# roboimplantschematic.net
KiCad netlist of a schematic drawn in EAGLE
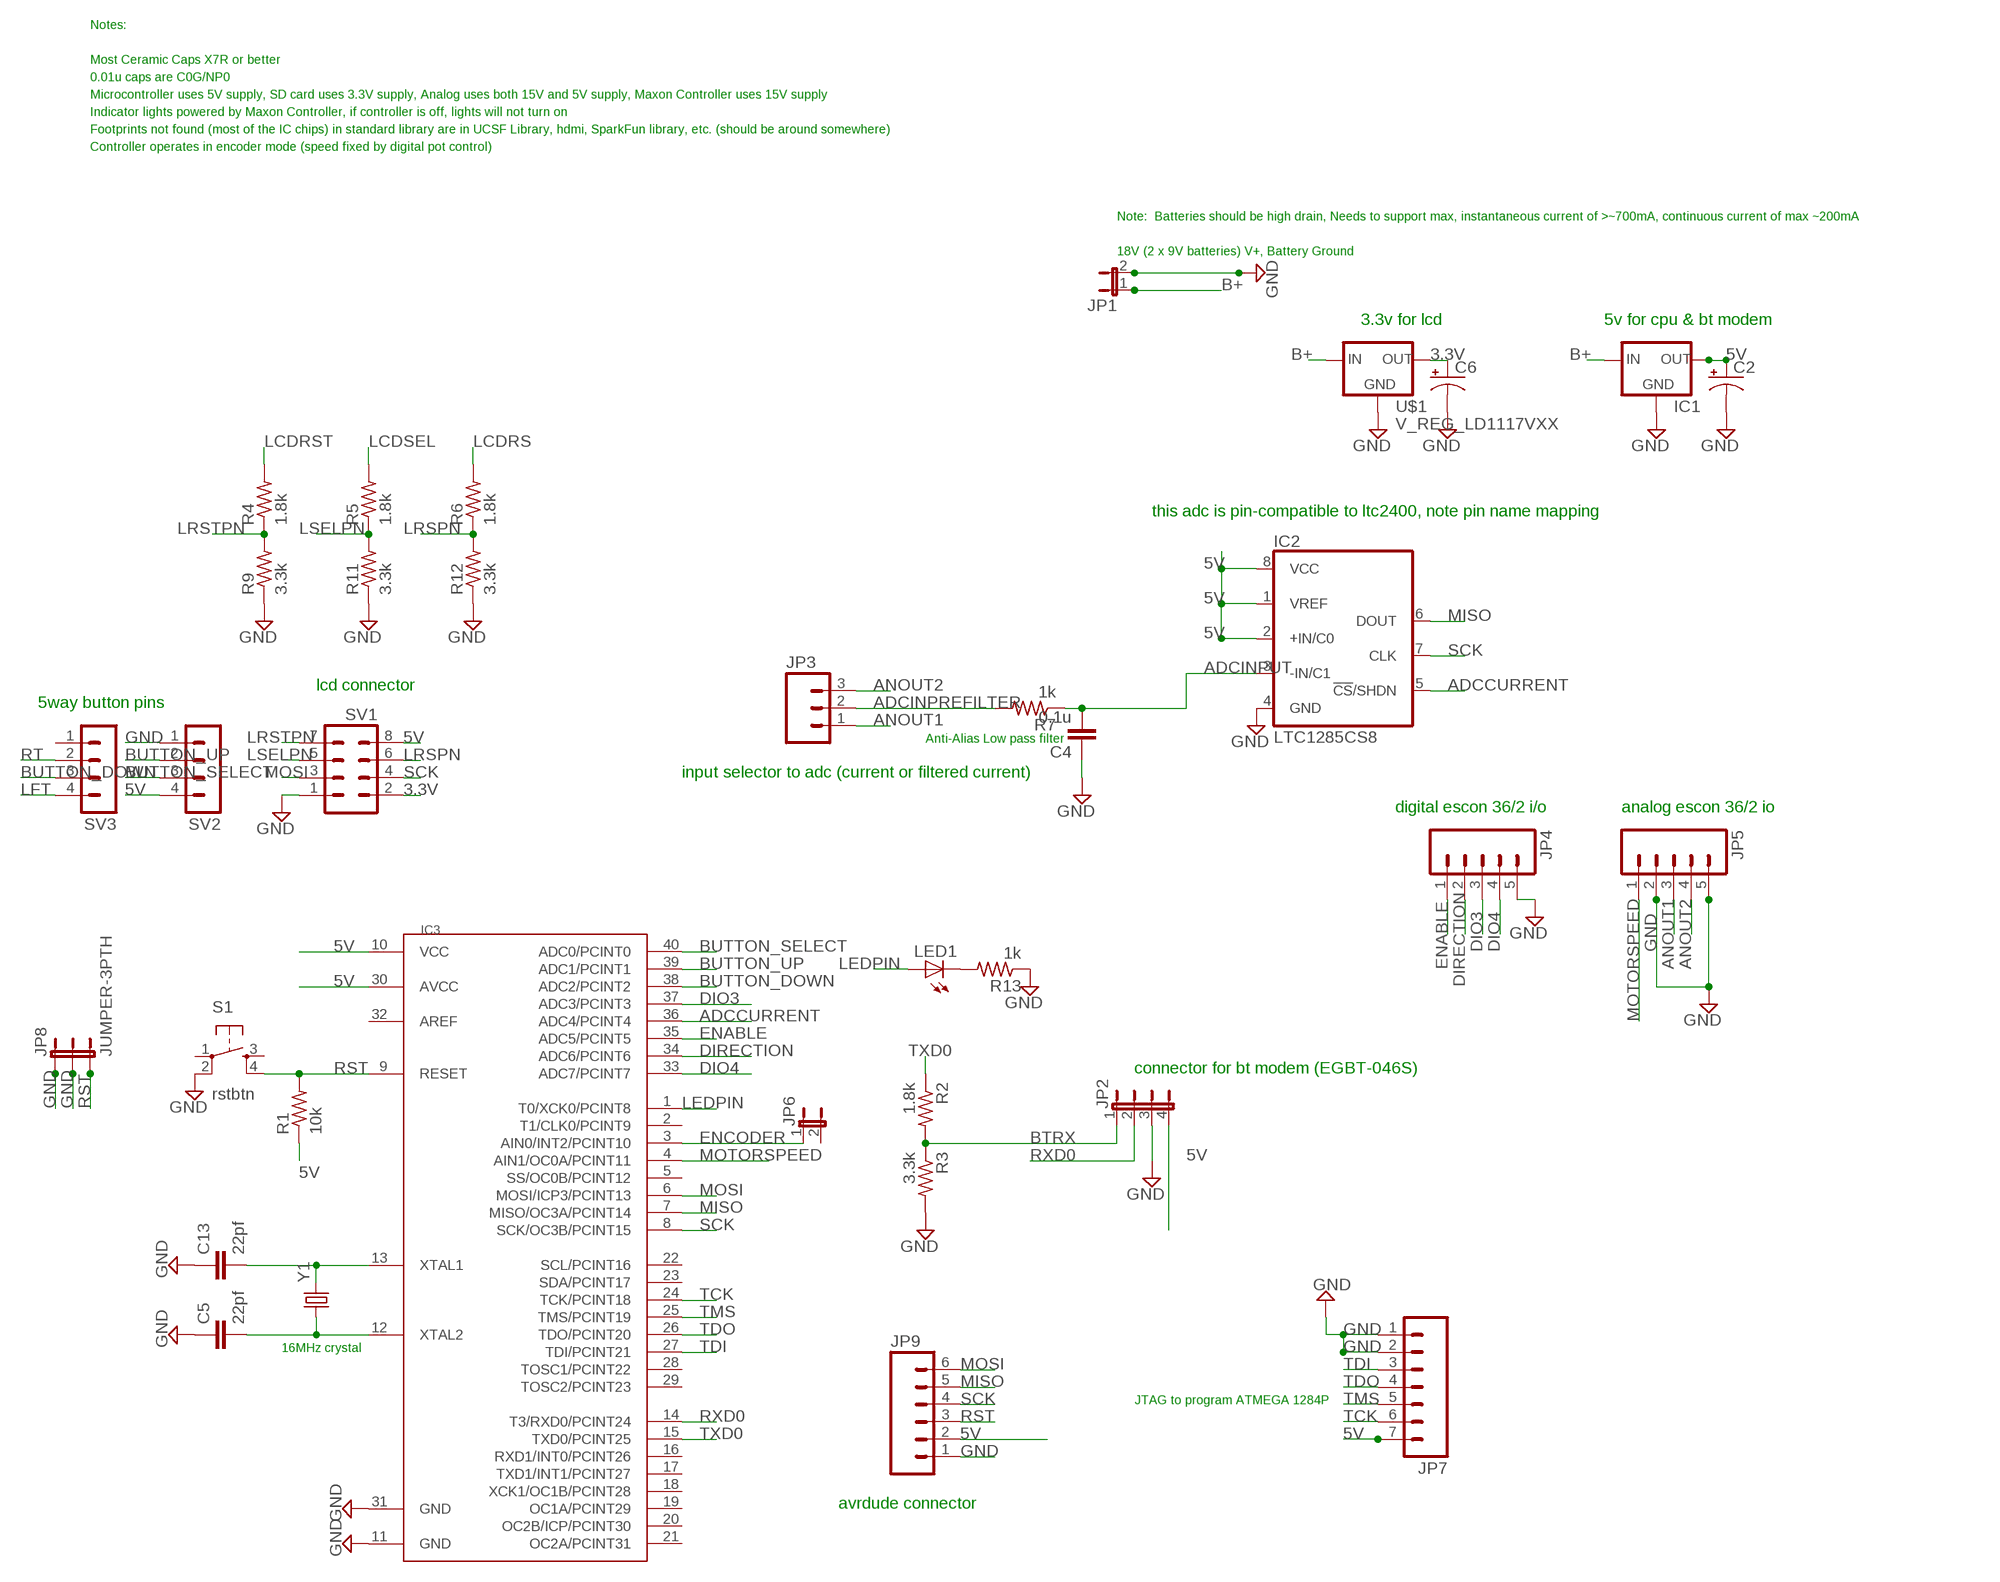
[diagram p0: schematic, sheet 1]

(export (version "E")
  (design (tool "Eeschema 10.0.6"))
  (components
    (comp (ref "C2")
      (value "CAP_POLPTH2")
      (footprint "eagle-import:CPOL-RADIAL-10UF-25V")
      (libsource (lib "eagle-import") (part "CAP_POLPTH2"))
    )
    (comp (ref "C4")
      (value "0.1u")
      (footprint "eagle-import:050X030_025")
      (libsource (lib "eagle-import") (part "050X030_0251"))
    )
    (comp (ref "C5")
      (value "22pf")
      (footprint "eagle-import:050X030_025")
      (libsource (lib "eagle-import") (part "050X030_0251"))
    )
    (comp (ref "C6")
      (value "CAP_POLPTH2")
      (footprint "eagle-import:CPOL-RADIAL-10UF-25V")
      (libsource (lib "eagle-import") (part "CAP_POLPTH2"))
    )
    (comp (ref "C13")
      (value "22pf")
      (footprint "eagle-import:050X030_025")
      (libsource (lib "eagle-import") (part "050X030_0251"))
    )
    (comp (ref "IC1")
      (value "V_REG_78XX-TO-220")
      (footprint "eagle-import:TO-220-ALT")
      (libsource (lib "eagle-import") (part "V_REG_78XX-TO-220"))
    )
    (comp (ref "IC2")
      (value "LTC1285CS8")
      (footprint "eagle-import:SOIC8")
      (libsource (lib "eagle-import") (part "LTC128CS85"))
    )
    (comp (ref "IC3")
      (value "MEGA1284P")
      (footprint "eagle-import:DIL40")
      (libsource (lib "eagle-import") (part "MEGA1284P"))
    )
    (comp (ref "JP1")
      (value "JP1E")
      (footprint "eagle-import:JP1")
      (libsource (lib "eagle-import") (part "JP1E"))
    )
    (comp (ref "JP2")
      (value "JP4E")
      (footprint "eagle-import:JP4")
      (libsource (lib "eagle-import") (part "JP4E"))
    )
    (comp (ref "JP3")
      (value "M03LOCK_LONGPADS")
      (footprint "eagle-import:1X03_LOCK_LONGPADS")
      (libsource (lib "eagle-import") (part "M03LOCK_LONGPADS"))
    )
    (comp (ref "JP4")
      (value "M05PTH_LONGPADS")
      (footprint "eagle-import:1X05_LONGPADS")
      (libsource (lib "eagle-import") (part "M05PTH_LONGPADS"))
    )
    (comp (ref "JP5")
      (value "M05PTH_LONGPADS")
      (footprint "eagle-import:1X05_LONGPADS")
      (libsource (lib "eagle-import") (part "M05PTH_LONGPADS"))
    )
    (comp (ref "JP6")
      (value "JUMPER-2PTH")
      (footprint "eagle-import:1X02")
      (libsource (lib "eagle-import") (part "JUMPER-2PTH"))
    )
    (comp (ref "JP7")
      (value "M07LOCK")
      (footprint "eagle-import:1X07_LOCK")
      (libsource (lib "eagle-import") (part "M07LOCK"))
    )
    (comp (ref "JP8")
      (value "JUMPER-3PTH")
      (footprint "eagle-import:1X03")
      (libsource (lib "eagle-import") (part "JUMPER-3PTH"))
    )
    (comp (ref "JP9")
      (value "M06SIP_LOCK")
      (footprint "eagle-import:1X06-SIP_LOCK")
      (libsource (lib "eagle-import") (part "M06SIP_LOCK"))
    )
    (comp (ref "LED1")
      (value "LED5MM")
      (footprint "eagle-import:LED5MM")
      (libsource (lib "eagle-import") (part "LED5MM"))
    )
    (comp (ref "R1")
      (value "10k")
      (footprint "eagle-import:0204_7")
      (libsource (lib "eagle-import") (part "R-US_0204/7"))
    )
    (comp (ref "R2")
      (value "1.8k")
      (footprint "eagle-import:0207_2V")
      (libsource (lib "eagle-import") (part "R-US_0207/2V"))
    )
    (comp (ref "R3")
      (value "3.3k")
      (footprint "eagle-import:0207_2V")
      (libsource (lib "eagle-import") (part "R-US_0207/2V"))
    )
    (comp (ref "R4")
      (value "1.8k")
      (footprint "eagle-import:0207_2V")
      (libsource (lib "eagle-import") (part "R-US_0207/2V"))
    )
    (comp (ref "R5")
      (value "1.8k")
      (footprint "eagle-import:0207_2V")
      (libsource (lib "eagle-import") (part "R-US_0207/2V"))
    )
    (comp (ref "R6")
      (value "1.8k")
      (footprint "eagle-import:0207_2V")
      (libsource (lib "eagle-import") (part "R-US_0207/2V"))
    )
    (comp (ref "R7")
      (value "1k")
      (footprint "eagle-import:0207_2V")
      (libsource (lib "eagle-import") (part "R-US_0207/2V"))
    )
    (comp (ref "R9")
      (value "3.3k")
      (footprint "eagle-import:0207_2V")
      (libsource (lib "eagle-import") (part "R-US_0207/2V"))
    )
    (comp (ref "R11")
      (value "3.3k")
      (footprint "eagle-import:0207_2V")
      (libsource (lib "eagle-import") (part "R-US_0207/2V"))
    )
    (comp (ref "R12")
      (value "3.3k")
      (footprint "eagle-import:0207_2V")
      (libsource (lib "eagle-import") (part "R-US_0207/2V"))
    )
    (comp (ref "R13")
      (value "1k")
      (footprint "eagle-import:0207_2V")
      (libsource (lib "eagle-import") (part "R-US_0207/2V"))
    )
    (comp (ref "S1")
      (value "rstbtn")
      (footprint "eagle-import:TACTILE-PTH")
      (libsource (lib "eagle-import") (part "TAC_SWITCHPTH"))
    )
    (comp (ref "SV1")
      (value "MA04-2")
      (footprint "eagle-import:MA04-2")
      (libsource (lib "eagle-import") (part "MA04-2"))
    )
    (comp (ref "SV2")
      (value "MA04-1")
      (footprint "eagle-import:MA04-1")
      (libsource (lib "eagle-import") (part "MA04-1"))
    )
    (comp (ref "SV3")
      (value "MA04-1")
      (footprint "eagle-import:MA04-1")
      (libsource (lib "eagle-import") (part "MA04-1"))
    )
    (comp (ref "U$1")
      (value "V_REG_LD1117VXX")
      (footprint "eagle-import:78XXL")
      (libsource (lib "eagle-import") (part "V_REG_LD1117VXX"))
    )
    (comp (ref "Y1")
      (value "CRYSTALHC49US")
      (footprint "eagle-import:HC49US")
      (libsource (lib "eagle-import") (part "CRYSTALHC49US"))
    )
  )
  (nets
    (net (code "1") (name "/3.3V") (class "Default")
      (node (ref "C6") (pin "1") (pinfunction "+_1") (pintype "passive"))
      (node (ref "SV1") (pin "2") (pinfunction "2_2") (pintype "passive"))
      (node (ref "U$1") (pin "GND") (pinfunction "OUT_GND") (pintype "output"))
    )
    (net (code "2") (name "/5V") (class "Default")
      (node (ref "C2") (pin "1") (pinfunction "+_1") (pintype "passive"))
      (node (ref "IC1") (pin "OUT") (pinfunction "OUT_OUT") (pintype "output"))
      (node (ref "IC2") (pin "1") (pinfunction "VREF_1") (pintype "input"))
      (node (ref "IC2") (pin "2") (pinfunction "+IN/C0_2") (pintype "input"))
      (node (ref "IC2") (pin "8") (pinfunction "VCC_8") (pintype "power_in"))
      (node (ref "IC3") (pin "10") (pinfunction "VCC_10") (pintype "bidirectional"))
      (node (ref "IC3") (pin "30") (pinfunction "AVCC_30") (pintype "bidirectional"))
      (node (ref "JP2") (pin "4") (pinfunction "4_4") (pintype "passive"))
      (node (ref "JP7") (pin "7") (pinfunction "7_7") (pintype "passive"))
      (node (ref "JP9") (pin "2") (pinfunction "2_2") (pintype "passive"))
      (node (ref "R1") (pin "1") (pinfunction "1_1") (pintype "passive"))
      (node (ref "SV1") (pin "8") (pinfunction "8_8") (pintype "passive"))
      (node (ref "SV2") (pin "4") (pinfunction "4_4") (pintype "passive"))
    )
    (net (code "3") (name "/ADCCURRENT") (class "Default")
      (node (ref "IC2") (pin "5") (pinfunction "~{CS}/SHDN_5") (pintype "output"))
      (node (ref "IC3") (pin "36") (pinfunction "ADC4/PCINT4_36") (pintype "bidirectional"))
    )
    (net (code "4") (name "/ADCINPREFILTER") (class "Default")
      (node (ref "JP3") (pin "2") (pinfunction "2_2") (pintype "passive"))
      (node (ref "R7") (pin "2") (pinfunction "2_2") (pintype "passive"))
    )
    (net (code "5") (name "/ADCINPUT") (class "Default")
      (node (ref "C4") (pin "2") (pinfunction "2_2") (pintype "passive"))
      (node (ref "IC2") (pin "3") (pinfunction "-IN/C1_3") (pintype "input"))
      (node (ref "R7") (pin "1") (pinfunction "1_1") (pintype "passive"))
    )
    (net (code "6") (name "/ANOUT1") (class "Default")
      (node (ref "JP3") (pin "1") (pinfunction "1_1") (pintype "passive"))
      (node (ref "JP5") (pin "3") (pinfunction "3_3") (pintype "passive"))
    )
    (net (code "7") (name "/ANOUT2") (class "Default")
      (node (ref "JP3") (pin "3") (pinfunction "3_3") (pintype "passive"))
      (node (ref "JP5") (pin "4") (pinfunction "4_4") (pintype "passive"))
    )
    (net (code "8") (name "/B+") (class "Default")
      (node (ref "IC1") (pin "IN") (pinfunction "IN_IN") (pintype "input"))
      (node (ref "JP1") (pin "1") (pinfunction "1_1") (pintype "passive"))
      (node (ref "U$1") (pin "OUT") (pinfunction "IN_OUT") (pintype "input"))
    )
    (net (code "9") (name "/BTRX") (class "Default")
      (node (ref "JP2") (pin "1") (pinfunction "1_1") (pintype "passive"))
      (node (ref "R2") (pin "2") (pinfunction "2_2") (pintype "passive"))
      (node (ref "R3") (pin "1") (pinfunction "1_1") (pintype "passive"))
    )
    (net (code "10") (name "/BUTTON_DOWN") (class "Default")
      (node (ref "IC3") (pin "38") (pinfunction "ADC2/PCINT2_38") (pintype "bidirectional"))
      (node (ref "SV3") (pin "3") (pinfunction "3_3") (pintype "passive"))
    )
    (net (code "11") (name "/BUTTON_SELECT") (class "Default")
      (node (ref "IC3") (pin "40") (pinfunction "ADC0/PCINT0_40") (pintype "bidirectional"))
      (node (ref "SV2") (pin "3") (pinfunction "3_3") (pintype "passive"))
    )
    (net (code "12") (name "/BUTTON_UP") (class "Default")
      (node (ref "IC3") (pin "39") (pinfunction "ADC1/PCINT1_39") (pintype "bidirectional"))
      (node (ref "SV2") (pin "2") (pinfunction "2_2") (pintype "passive"))
    )
    (net (code "13") (name "/DIO3") (class "Default")
      (node (ref "IC3") (pin "37") (pinfunction "ADC3/PCINT3_37") (pintype "bidirectional"))
      (node (ref "JP4") (pin "3") (pinfunction "3_3") (pintype "passive"))
    )
    (net (code "14") (name "/DIO4") (class "Default")
      (node (ref "IC3") (pin "33") (pinfunction "ADC7/PCINT7_33") (pintype "bidirectional"))
      (node (ref "JP4") (pin "4") (pinfunction "4_4") (pintype "passive"))
    )
    (net (code "15") (name "/DIRECTION") (class "Default")
      (node (ref "IC3") (pin "34") (pinfunction "ADC6/PCINT6_34") (pintype "bidirectional"))
      (node (ref "JP4") (pin "2") (pinfunction "2_2") (pintype "passive"))
    )
    (net (code "16") (name "/ENABLE") (class "Default")
      (node (ref "IC3") (pin "35") (pinfunction "ADC5/PCINT5_35") (pintype "bidirectional"))
      (node (ref "JP4") (pin "1") (pinfunction "1_1") (pintype "passive"))
    )
    (net (code "17") (name "/ENCODER") (class "Default")
      (node (ref "IC3") (pin "3") (pinfunction "AIN0/INT2/PCINT10_3") (pintype "bidirectional"))
      (node (ref "JP6") (pin "1") (pinfunction "1_1") (pintype "passive"))
    )
    (net (code "18") (name "/LCDRS") (class "Default")
      (node (ref "R6") (pin "2") (pinfunction "2_2") (pintype "passive"))
    )
    (net (code "19") (name "/LCDRST") (class "Default")
      (node (ref "R4") (pin "2") (pinfunction "2_2") (pintype "passive"))
    )
    (net (code "20") (name "/LCDSEL") (class "Default")
      (node (ref "R5") (pin "2") (pinfunction "2_2") (pintype "passive"))
    )
    (net (code "21") (name "/LEDPIN") (class "Default")
      (node (ref "IC3") (pin "1") (pinfunction "T0/XCK0/PCINT8_1") (pintype "bidirectional"))
      (node (ref "LED1") (pin "A") (pinfunction "A_A") (pintype "passive"))
    )
    (net (code "22") (name "/LFT") (class "Default")
      (node (ref "SV3") (pin "4") (pinfunction "4_4") (pintype "passive"))
    )
    (net (code "23") (name "/LRSPN") (class "Default")
      (node (ref "R12") (pin "2") (pinfunction "2_2") (pintype "passive"))
      (node (ref "R6") (pin "1") (pinfunction "1_1") (pintype "passive"))
      (node (ref "SV1") (pin "6") (pinfunction "6_6") (pintype "passive"))
    )
    (net (code "24") (name "/LRSTPN") (class "Default")
      (node (ref "R4") (pin "1") (pinfunction "1_1") (pintype "passive"))
      (node (ref "R9") (pin "2") (pinfunction "2_2") (pintype "passive"))
      (node (ref "SV1") (pin "7") (pinfunction "7_7") (pintype "passive"))
    )
    (net (code "25") (name "/LSELPN") (class "Default")
      (node (ref "R11") (pin "2") (pinfunction "2_2") (pintype "passive"))
      (node (ref "R5") (pin "1") (pinfunction "1_1") (pintype "passive"))
      (node (ref "SV1") (pin "5") (pinfunction "5_5") (pintype "passive"))
    )
    (net (code "26") (name "/MISO") (class "Default")
      (node (ref "IC2") (pin "6") (pinfunction "DOUT_6") (pintype "output"))
      (node (ref "IC3") (pin "7") (pinfunction "MISO/OC3A/PCINT14_7") (pintype "bidirectional"))
      (node (ref "JP9") (pin "5") (pinfunction "5_5") (pintype "passive"))
    )
    (net (code "27") (name "/MOSI") (class "Default")
      (node (ref "IC3") (pin "6") (pinfunction "MOSI/ICP3/PCINT13_6") (pintype "bidirectional"))
      (node (ref "JP9") (pin "6") (pinfunction "6_6") (pintype "passive"))
      (node (ref "SV1") (pin "3") (pinfunction "3_3") (pintype "passive"))
    )
    (net (code "28") (name "/MOTORSPEED") (class "Default")
      (node (ref "IC3") (pin "4") (pinfunction "AIN1/OC0A/PCINT11_4") (pintype "bidirectional"))
      (node (ref "JP5") (pin "1") (pinfunction "1_1") (pintype "passive"))
    )
    (net (code "29") (name "/RST") (class "Default")
      (node (ref "IC3") (pin "9") (pinfunction "RESET_9") (pintype "bidirectional"))
      (node (ref "JP8") (pin "3") (pinfunction "3_3") (pintype "passive"))
      (node (ref "JP9") (pin "3") (pinfunction "3_3") (pintype "passive"))
      (node (ref "R1") (pin "2") (pinfunction "2_2") (pintype "passive"))
      (node (ref "S1") (pin "4") (pinfunction "4_4") (pintype "passive"))
    )
    (net (code "30") (name "/RT") (class "Default")
      (node (ref "SV3") (pin "2") (pinfunction "2_2") (pintype "passive"))
    )
    (net (code "31") (name "/RXD0") (class "Default")
      (node (ref "IC3") (pin "14") (pinfunction "T3/RXD0/PCINT24_14") (pintype "bidirectional"))
      (node (ref "JP2") (pin "2") (pinfunction "2_2") (pintype "passive"))
    )
    (net (code "32") (name "/SCK") (class "Default")
      (node (ref "IC2") (pin "7") (pinfunction "CLK_7") (pintype "input"))
      (node (ref "IC3") (pin "8") (pinfunction "SCK/OC3B/PCINT15_8") (pintype "bidirectional"))
      (node (ref "JP9") (pin "4") (pinfunction "4_4") (pintype "passive"))
      (node (ref "SV1") (pin "4") (pinfunction "4_4") (pintype "passive"))
    )
    (net (code "33") (name "/TCK") (class "Default")
      (node (ref "IC3") (pin "24") (pinfunction "TCK/PCINT18_24") (pintype "bidirectional"))
      (node (ref "JP7") (pin "6") (pinfunction "6_6") (pintype "passive"))
    )
    (net (code "34") (name "/TDI") (class "Default")
      (node (ref "IC3") (pin "27") (pinfunction "TDI/PCINT21_27") (pintype "bidirectional"))
      (node (ref "JP7") (pin "3") (pinfunction "3_3") (pintype "passive"))
    )
    (net (code "35") (name "/TDO") (class "Default")
      (node (ref "IC3") (pin "26") (pinfunction "TDO/PCINT20_26") (pintype "bidirectional"))
      (node (ref "JP7") (pin "4") (pinfunction "4_4") (pintype "passive"))
    )
    (net (code "36") (name "/TMS") (class "Default")
      (node (ref "IC3") (pin "25") (pinfunction "TMS/PCINT19_25") (pintype "bidirectional"))
      (node (ref "JP7") (pin "5") (pinfunction "5_5") (pintype "passive"))
    )
    (net (code "37") (name "/TXD0") (class "Default")
      (node (ref "IC3") (pin "15") (pinfunction "TXD0/PCINT25_15") (pintype "bidirectional"))
      (node (ref "R2") (pin "1") (pinfunction "1_1") (pintype "passive"))
    )
    (net (code "38") (name "GND") (class "Default")
      (node (ref "C13") (pin "1") (pinfunction "1_1") (pintype "passive"))
      (node (ref "C2") (pin "2") (pinfunction "-_2") (pintype "passive"))
      (node (ref "C4") (pin "1") (pinfunction "1_1") (pintype "passive"))
      (node (ref "C5") (pin "1") (pinfunction "1_1") (pintype "passive"))
      (node (ref "C6") (pin "2") (pinfunction "-_2") (pintype "passive"))
      (node (ref "IC1") (pin "GND") (pinfunction "GND_GND") (pintype "input"))
      (node (ref "IC2") (pin "4") (pinfunction "GND_4") (pintype "power_in"))
      (node (ref "IC3") (pin "11") (pinfunction "GND_11") (pintype "bidirectional"))
      (node (ref "IC3") (pin "31") (pinfunction "GND_31") (pintype "bidirectional"))
      (node (ref "JP1") (pin "2") (pinfunction "2_2") (pintype "passive"))
      (node (ref "JP2") (pin "3") (pinfunction "3_3") (pintype "passive"))
      (node (ref "JP4") (pin "5") (pinfunction "5_5") (pintype "passive"))
      (node (ref "JP5") (pin "2") (pinfunction "2_2") (pintype "passive"))
      (node (ref "JP5") (pin "5") (pinfunction "5_5") (pintype "passive"))
      (node (ref "JP7") (pin "1") (pinfunction "1_1") (pintype "passive"))
      (node (ref "JP7") (pin "2") (pinfunction "2_2") (pintype "passive"))
      (node (ref "JP8") (pin "1") (pinfunction "1_1") (pintype "passive"))
      (node (ref "JP8") (pin "2") (pinfunction "2_2") (pintype "passive"))
      (node (ref "JP9") (pin "1") (pinfunction "1_1") (pintype "passive"))
      (node (ref "R11") (pin "1") (pinfunction "1_1") (pintype "passive"))
      (node (ref "R12") (pin "1") (pinfunction "1_1") (pintype "passive"))
      (node (ref "R13") (pin "1") (pinfunction "1_1") (pintype "passive"))
      (node (ref "R3") (pin "2") (pinfunction "2_2") (pintype "passive"))
      (node (ref "R9") (pin "1") (pinfunction "1_1") (pintype "passive"))
      (node (ref "S1") (pin "2") (pinfunction "2_2") (pintype "passive"))
      (node (ref "SV1") (pin "1") (pinfunction "1_1") (pintype "passive"))
      (node (ref "SV2") (pin "1") (pinfunction "1_1") (pintype "passive"))
      (node (ref "U$1") (pin "IN") (pinfunction "GND_IN") (pintype "input"))
    )
    (net (code "39") (name "Net-(IC3-XTAL1)") (class "Default")
      (node (ref "C13") (pin "2") (pinfunction "2_2") (pintype "passive"))
      (node (ref "IC3") (pin "13") (pinfunction "XTAL1_13") (pintype "bidirectional"))
      (node (ref "Y1") (pin "2") (pinfunction "2_2") (pintype "passive"))
    )
    (net (code "40") (name "Net-(IC3-XTAL2)") (class "Default")
      (node (ref "C5") (pin "2") (pinfunction "2_2") (pintype "passive"))
      (node (ref "IC3") (pin "12") (pinfunction "XTAL2_12") (pintype "bidirectional"))
      (node (ref "Y1") (pin "1") (pinfunction "1_1") (pintype "passive"))
    )
    (net (code "41") (name "Net-(LED1-C)") (class "Default")
      (node (ref "LED1") (pin "K") (pinfunction "C_K") (pintype "passive"))
      (node (ref "R13") (pin "2") (pinfunction "2_2") (pintype "passive"))
    )
    (net (code "42") (name "unconnected-(IC3-AREF-Pad32)") (class "Default")
      (node (ref "IC3") (pin "32") (pinfunction "AREF_32") (pintype "bidirectional"))
    )
    (net (code "43") (name "unconnected-(IC3-OC1A{slash}PCINT29-Pad19)") (class "Default")
      (node (ref "IC3") (pin "19") (pinfunction "OC1A/PCINT29_19") (pintype "bidirectional"))
    )
    (net (code "44") (name "unconnected-(IC3-OC2A{slash}PCINT31-Pad21)") (class "Default")
      (node (ref "IC3") (pin "21") (pinfunction "OC2A/PCINT31_21") (pintype "bidirectional"))
    )
    (net (code "45") (name "unconnected-(IC3-OC2B{slash}ICP{slash}PCINT30-Pad20)") (class "Default")
      (node (ref "IC3") (pin "20") (pinfunction "OC2B/ICP/PCINT30_20") (pintype "bidirectional"))
    )
    (net (code "46") (name "unconnected-(IC3-RXD1{slash}INT0{slash}PCINT26-Pad16)") (class "Default")
      (node (ref "IC3") (pin "16") (pinfunction "RXD1/INT0/PCINT26_16") (pintype "bidirectional"))
    )
    (net (code "47") (name "unconnected-(IC3-SCL{slash}PCINT16-Pad22)") (class "Default")
      (node (ref "IC3") (pin "22") (pinfunction "SCL/PCINT16_22") (pintype "bidirectional"))
    )
    (net (code "48") (name "unconnected-(IC3-SDA{slash}PCINT17-Pad23)") (class "Default")
      (node (ref "IC3") (pin "23") (pinfunction "SDA/PCINT17_23") (pintype "bidirectional"))
    )
    (net (code "49") (name "unconnected-(IC3-SS{slash}OC0B{slash}PCINT12-Pad5)") (class "Default")
      (node (ref "IC3") (pin "5") (pinfunction "SS/OC0B/PCINT12_5") (pintype "bidirectional"))
    )
    (net (code "50") (name "unconnected-(IC3-T1{slash}CLK0{slash}PCINT9-Pad2)") (class "Default")
      (node (ref "IC3") (pin "2") (pinfunction "T1/CLK0/PCINT9_2") (pintype "bidirectional"))
    )
    (net (code "51") (name "unconnected-(IC3-TOSC1{slash}PCINT22-Pad28)") (class "Default")
      (node (ref "IC3") (pin "28") (pinfunction "TOSC1/PCINT22_28") (pintype "bidirectional"))
    )
    (net (code "52") (name "unconnected-(IC3-TOSC2{slash}PCINT23-Pad29)") (class "Default")
      (node (ref "IC3") (pin "29") (pinfunction "TOSC2/PCINT23_29") (pintype "bidirectional"))
    )
    (net (code "53") (name "unconnected-(IC3-TXD1{slash}INT1{slash}PCINT27-Pad17)") (class "Default")
      (node (ref "IC3") (pin "17") (pinfunction "TXD1/INT1/PCINT27_17") (pintype "bidirectional"))
    )
    (net (code "54") (name "unconnected-(IC3-XCK1{slash}OC1B{slash}PCINT28-Pad18)") (class "Default")
      (node (ref "IC3") (pin "18") (pinfunction "XCK1/OC1B/PCINT28_18") (pintype "bidirectional"))
    )
    (net (code "55") (name "unconnected-(JP6-Pad2)") (class "Default")
      (node (ref "JP6") (pin "2") (pinfunction "2_2") (pintype "passive"))
    )
    (net (code "56") (name "unconnected-(S1-Pad1)") (class "Default")
      (node (ref "S1") (pin "1") (pinfunction "1_1") (pintype "passive"))
    )
    (net (code "57") (name "unconnected-(S1-Pad3)") (class "Default")
      (node (ref "S1") (pin "3") (pinfunction "3_3") (pintype "passive"))
    )
    (net (code "58") (name "unconnected-(SV3-Pad1)") (class "Default")
      (node (ref "SV3") (pin "1") (pinfunction "1_1") (pintype "passive"))
    )
  )
)
